# analogBoardV1_2.net
KiCad netlist of a schematic drawn in EAGLE
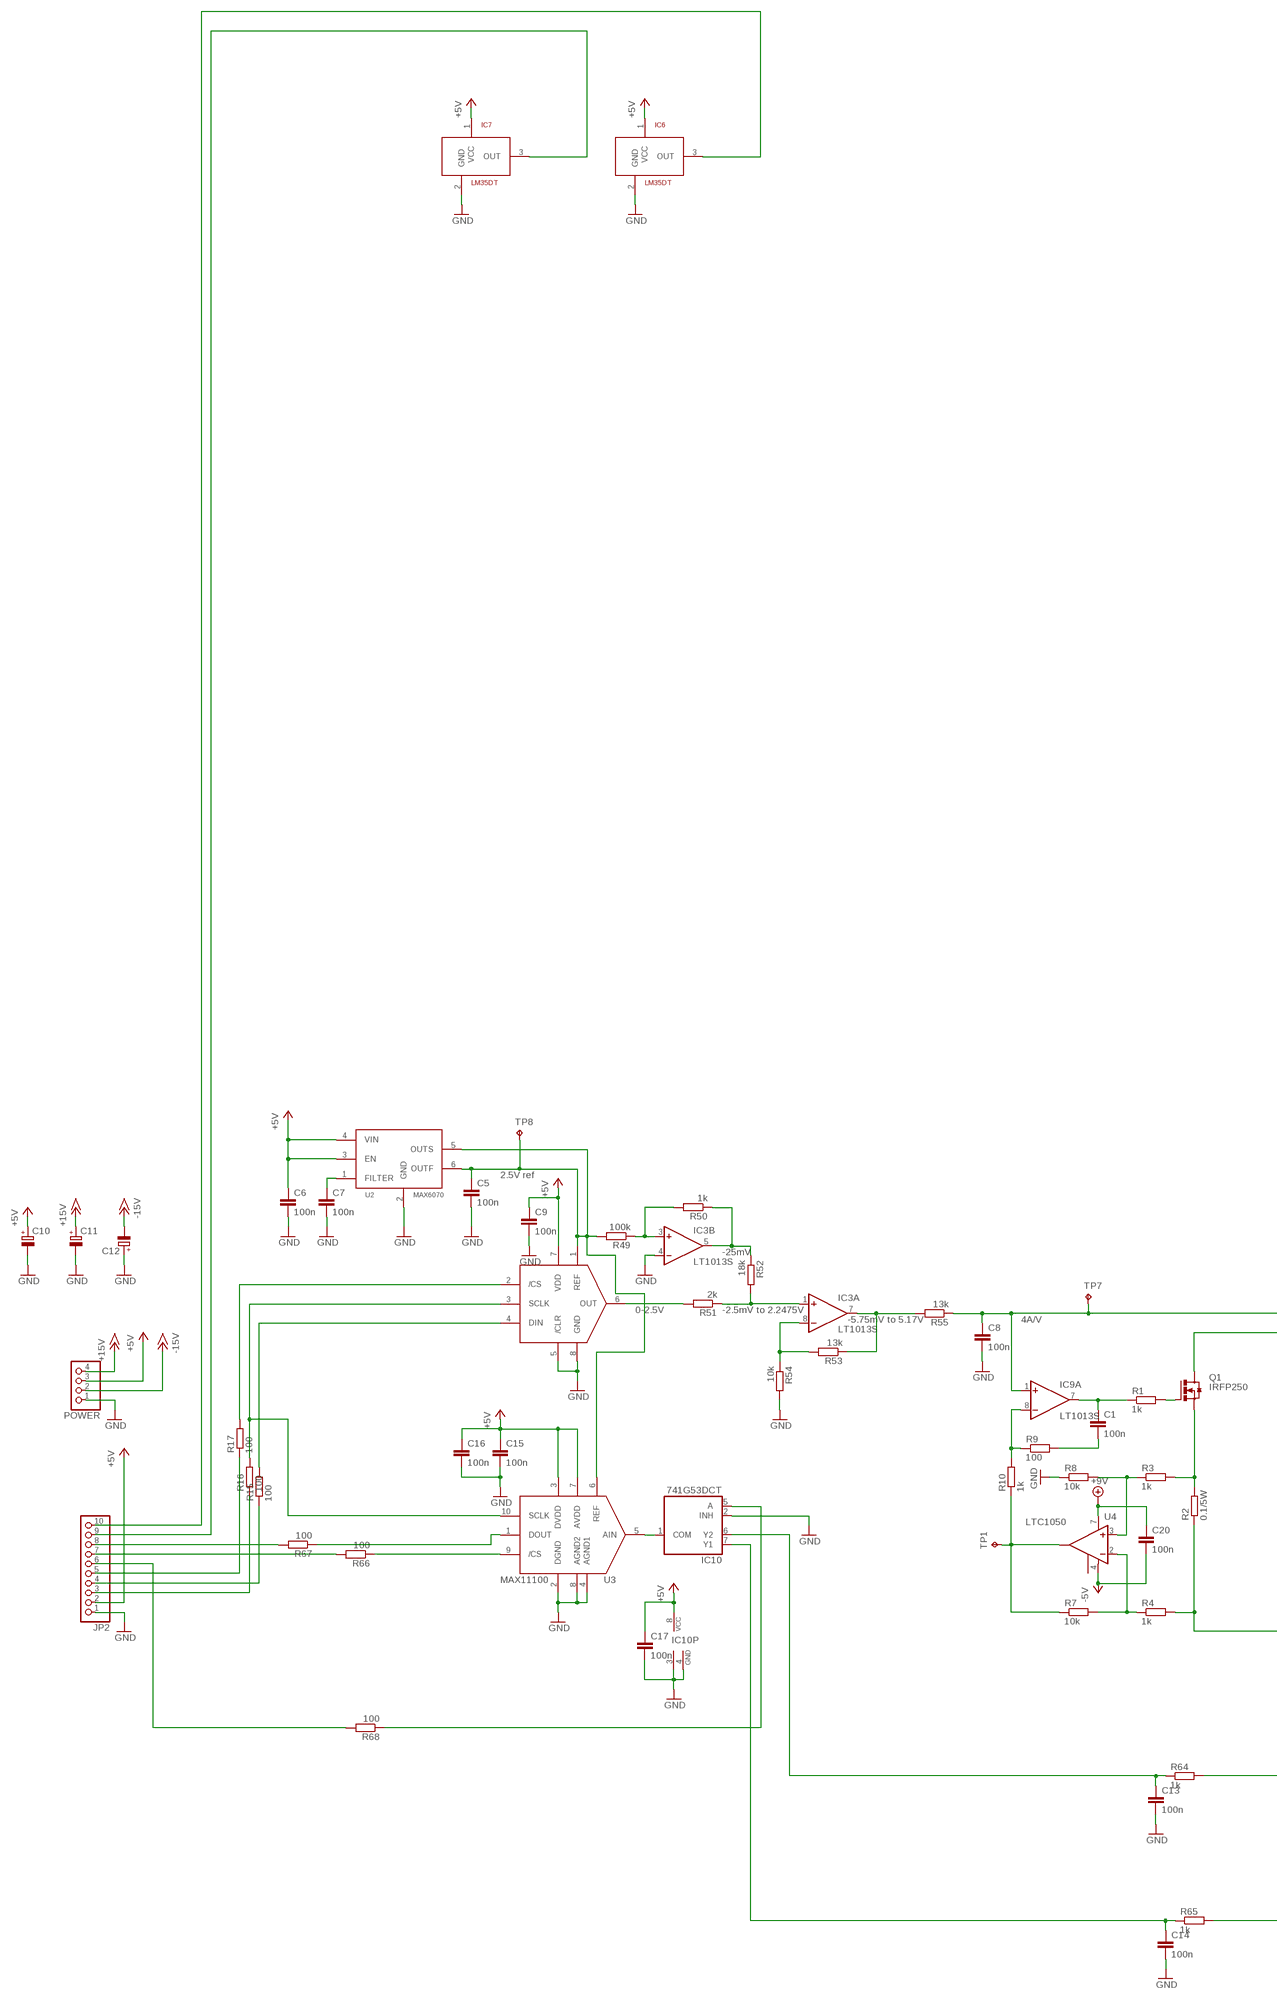
[diagram p0: schematic, sheet 1, part 1 of 2]
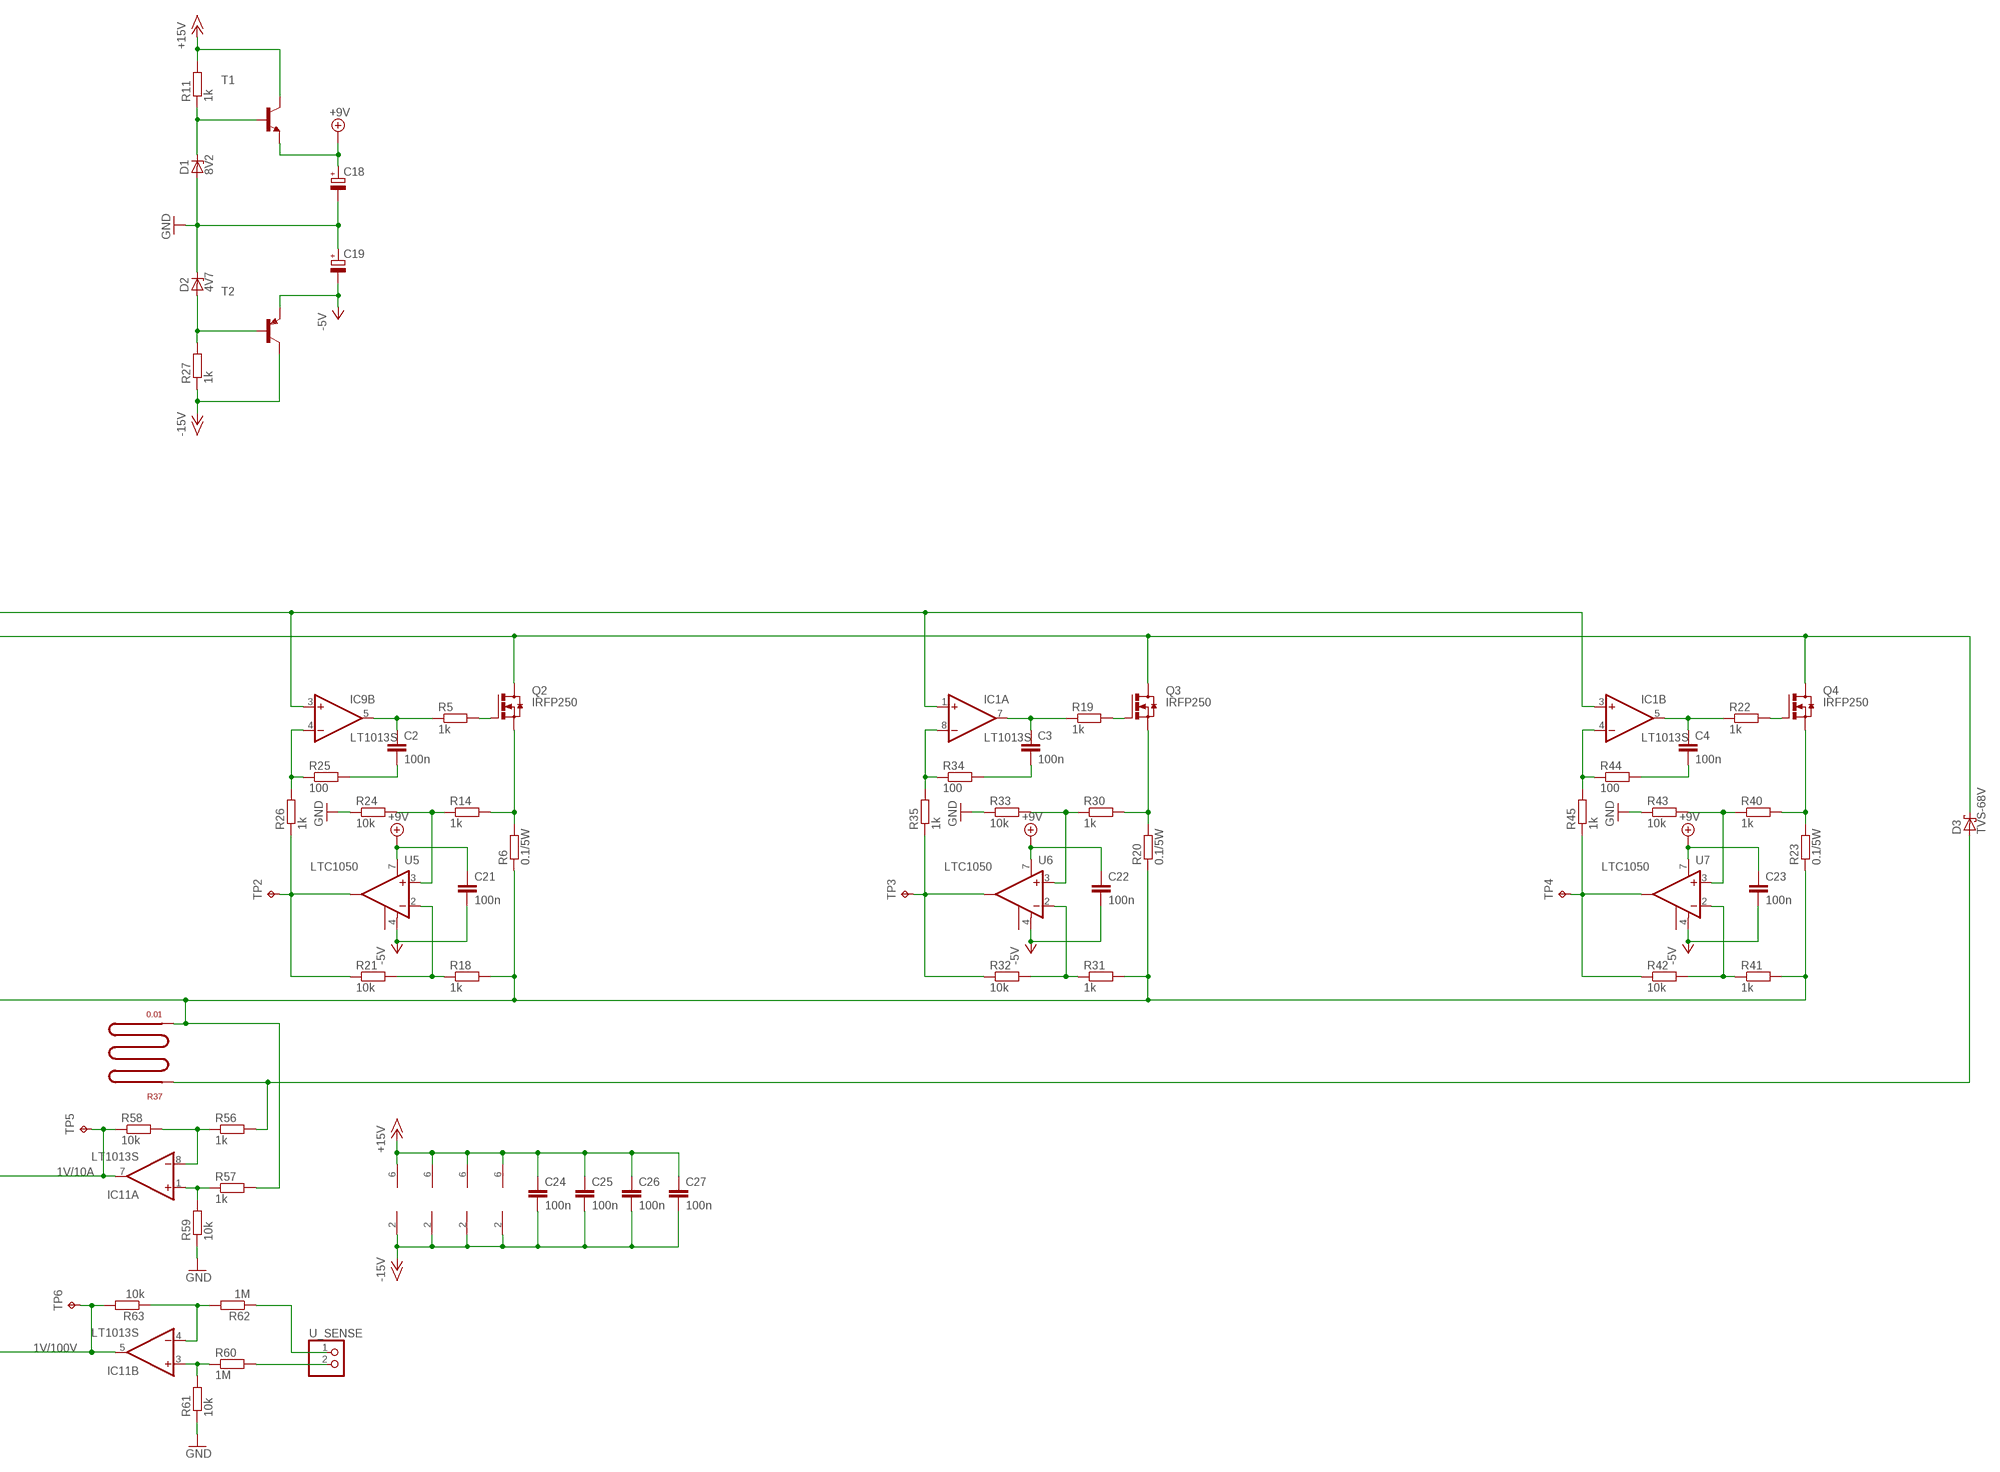
[diagram p1: schematic, sheet 1, part 2 of 2]

(export (version "E")
  (design (tool "Eeschema 10.0.6"))
  (components
    (comp (ref "C1")
      (value "100n")
      (footprint "eagle-import:C0603K")
      (libsource (lib "eagle-import") (part "C-EUC0603K"))
    )
    (comp (ref "C2")
      (value "100n")
      (footprint "eagle-import:C0603K")
      (libsource (lib "eagle-import") (part "C-EUC0603K"))
    )
    (comp (ref "C3")
      (value "100n")
      (footprint "eagle-import:C0603K")
      (libsource (lib "eagle-import") (part "C-EUC0603K"))
    )
    (comp (ref "C4")
      (value "100n")
      (footprint "eagle-import:C0603K")
      (libsource (lib "eagle-import") (part "C-EUC0603K"))
    )
    (comp (ref "C5")
      (value "100n")
      (footprint "eagle-import:C0603K")
      (libsource (lib "eagle-import") (part "C-EUC0603K"))
    )
    (comp (ref "C6")
      (value "100n")
      (footprint "eagle-import:C0603K")
      (libsource (lib "eagle-import") (part "C-EUC0603K"))
    )
    (comp (ref "C7")
      (value "100n")
      (footprint "eagle-import:C0603K")
      (libsource (lib "eagle-import") (part "C-EUC0603K"))
    )
    (comp (ref "C8")
      (value "100n")
      (footprint "eagle-import:C0603K")
      (libsource (lib "eagle-import") (part "C-EUC0603K"))
    )
    (comp (ref "C9")
      (value "100n")
      (footprint "eagle-import:C0603K")
      (libsource (lib "eagle-import") (part "C-EUC0603K"))
    )
    (comp (ref "C10")
      (value "CPOL-EUE2.5-6")
      (footprint "eagle-import:E2,5-6")
      (libsource (lib "eagle-import") (part "CPOL-EUE2.5-6"))
    )
    (comp (ref "C11")
      (value "CPOL-EUE2.5-6")
      (footprint "eagle-import:E2,5-6")
      (libsource (lib "eagle-import") (part "CPOL-EUE2.5-6"))
    )
    (comp (ref "C12")
      (value "CPOL-EUE2.5-6")
      (footprint "eagle-import:E2,5-6")
      (libsource (lib "eagle-import") (part "CPOL-EUE2.5-6"))
    )
    (comp (ref "C13")
      (value "100n")
      (footprint "eagle-import:C0603K")
      (libsource (lib "eagle-import") (part "C-EUC0603K"))
    )
    (comp (ref "C14")
      (value "100n")
      (footprint "eagle-import:C0603K")
      (libsource (lib "eagle-import") (part "C-EUC0603K"))
    )
    (comp (ref "C15")
      (value "100n")
      (footprint "eagle-import:C0603K")
      (libsource (lib "eagle-import") (part "C-EUC0603K"))
    )
    (comp (ref "C16")
      (value "100n")
      (footprint "eagle-import:C0603K")
      (libsource (lib "eagle-import") (part "C-EUC0603K"))
    )
    (comp (ref "C17")
      (value "100n")
      (footprint "eagle-import:C0603K")
      (libsource (lib "eagle-import") (part "C-EUC0603K"))
    )
    (comp (ref "C18")
      (value "CPOL-EUE2.5-6")
      (footprint "eagle-import:E2,5-6")
      (libsource (lib "eagle-import") (part "CPOL-EUE2.5-6"))
    )
    (comp (ref "C19")
      (value "CPOL-EUE2.5-6")
      (footprint "eagle-import:E2,5-6")
      (libsource (lib "eagle-import") (part "CPOL-EUE2.5-6"))
    )
    (comp (ref "C20")
      (value "100n")
      (footprint "eagle-import:C0603K")
      (libsource (lib "eagle-import") (part "C-EUC0603K"))
    )
    (comp (ref "C21")
      (value "100n")
      (footprint "eagle-import:C0603K")
      (libsource (lib "eagle-import") (part "C-EUC0603K"))
    )
    (comp (ref "C22")
      (value "100n")
      (footprint "eagle-import:C0603K")
      (libsource (lib "eagle-import") (part "C-EUC0603K"))
    )
    (comp (ref "C23")
      (value "100n")
      (footprint "eagle-import:C0603K")
      (libsource (lib "eagle-import") (part "C-EUC0603K"))
    )
    (comp (ref "C24")
      (value "100n")
      (footprint "eagle-import:C0603K")
      (libsource (lib "eagle-import") (part "C-EUC0603K"))
    )
    (comp (ref "C25")
      (value "100n")
      (footprint "eagle-import:C0603K")
      (libsource (lib "eagle-import") (part "C-EUC0603K"))
    )
    (comp (ref "C26")
      (value "100n")
      (footprint "eagle-import:C0603K")
      (libsource (lib "eagle-import") (part "C-EUC0603K"))
    )
    (comp (ref "C27")
      (value "100n")
      (footprint "eagle-import:C0603K")
      (libsource (lib "eagle-import") (part "C-EUC0603K"))
    )
    (comp (ref "D1")
      (value "8V2")
      (footprint "eagle-import:SOT23")
      (libsource (lib "eagle-import") (part "ZENER-DIODESOT23"))
    )
    (comp (ref "D2")
      (value "4V7")
      (footprint "eagle-import:SOT23")
      (libsource (lib "eagle-import") (part "ZENER-DIODESOT23"))
    )
    (comp (ref "D3")
      (value "TVS-68V")
      (footprint "eagle-import:CB429-15")
      (libsource (lib "eagle-import") (part "SCHOTTKY-DIODECB429-15"))
    )
    (comp (ref "IC1")
      (value "LT1013S")
      (footprint "eagle-import:SO08")
      (libsource (lib "eagle-import") (part "LT1013S"))
    )
    (comp (ref "IC3")
      (value "LT1013S")
      (footprint "eagle-import:SO08")
      (libsource (lib "eagle-import") (part "LT1013S"))
    )
    (comp (ref "IC6")
      (value "LM35DT")
      (footprint "eagle-import:TO220V")
      (libsource (lib "eagle-import") (part "LM35DT"))
    )
    (comp (ref "IC7")
      (value "LM35DT")
      (footprint "eagle-import:TO220V")
      (libsource (lib "eagle-import") (part "LM35DT"))
    )
    (comp (ref "IC9")
      (value "LT1013S")
      (footprint "eagle-import:SO08")
      (libsource (lib "eagle-import") (part "LT1013S"))
    )
    (comp (ref "IC10")
      (value "741G53DCT")
      (footprint "eagle-import:DCT_R-PDSO-G8")
      (libsource (lib "eagle-import") (part "741G53DCT"))
    )
    (comp (ref "IC11")
      (value "LT1013S")
      (footprint "eagle-import:SO08")
      (libsource (lib "eagle-import") (part "LT1013S"))
    )
    (comp (ref "JP2")
      (value "PINHD-1X10")
      (footprint "eagle-import:1X10")
      (libsource (lib "eagle-import") (part "PINHD-1X10"))
    )
    (comp (ref "POWER")
      (value "PINHD-1X4")
      (footprint "eagle-import:1X04")
      (libsource (lib "eagle-import") (part "PINHD-1X4"))
    )
    (comp (ref "Q1")
      (value "IRFP250")
      (footprint "eagle-import:TO-247AD-V")
      (libsource (lib "eagle-import") (part "IRFP250"))
    )
    (comp (ref "Q2")
      (value "IRFP250")
      (footprint "eagle-import:TO-247AD-V")
      (libsource (lib "eagle-import") (part "IRFP250"))
    )
    (comp (ref "Q3")
      (value "IRFP250")
      (footprint "eagle-import:TO-247AD-V")
      (libsource (lib "eagle-import") (part "IRFP250"))
    )
    (comp (ref "Q4")
      (value "IRFP250")
      (footprint "eagle-import:TO-247AD-V")
      (libsource (lib "eagle-import") (part "IRFP250"))
    )
    (comp (ref "R1")
      (value "1k")
      (footprint "eagle-import:R0603")
      (libsource (lib "eagle-import") (part "R-EU_R0603"))
    )
    (comp (ref "R2")
      (value "0.1/5W")
      (footprint "eagle-import:5WAXIAL")
      (libsource (lib "eagle-import") (part "5WAXIAL"))
    )
    (comp (ref "R3")
      (value "1k")
      (footprint "eagle-import:R0603")
      (libsource (lib "eagle-import") (part "R-EU_R0603"))
    )
    (comp (ref "R4")
      (value "1k")
      (footprint "eagle-import:R0603")
      (libsource (lib "eagle-import") (part "R-EU_R0603"))
    )
    (comp (ref "R5")
      (value "1k")
      (footprint "eagle-import:R0603")
      (libsource (lib "eagle-import") (part "R-EU_R0603"))
    )
    (comp (ref "R6")
      (value "0.1/5W")
      (footprint "eagle-import:5WAXIAL")
      (libsource (lib "eagle-import") (part "5WAXIAL"))
    )
    (comp (ref "R7")
      (value "10k")
      (footprint "eagle-import:R0603")
      (libsource (lib "eagle-import") (part "R-EU_R0603"))
    )
    (comp (ref "R8")
      (value "10k")
      (footprint "eagle-import:R0603")
      (libsource (lib "eagle-import") (part "R-EU_R0603"))
    )
    (comp (ref "R9")
      (value "100")
      (footprint "eagle-import:R0603")
      (libsource (lib "eagle-import") (part "R-EU_R0603"))
    )
    (comp (ref "R10")
      (value "1k")
      (footprint "eagle-import:R0603")
      (libsource (lib "eagle-import") (part "R-EU_R0603"))
    )
    (comp (ref "R11")
      (value "1k")
      (footprint "eagle-import:R0603")
      (libsource (lib "eagle-import") (part "R-EU_R0603"))
    )
    (comp (ref "R14")
      (value "1k")
      (footprint "eagle-import:R0603")
      (libsource (lib "eagle-import") (part "R-EU_R0603"))
    )
    (comp (ref "R15")
      (value "100")
      (footprint "eagle-import:R0603")
      (libsource (lib "eagle-import") (part "R-EU_R0603"))
    )
    (comp (ref "R16")
      (value "100")
      (footprint "eagle-import:R0603")
      (libsource (lib "eagle-import") (part "R-EU_R0603"))
    )
    (comp (ref "R17")
      (value "100")
      (footprint "eagle-import:R0603")
      (libsource (lib "eagle-import") (part "R-EU_R0603"))
    )
    (comp (ref "R18")
      (value "1k")
      (footprint "eagle-import:R0603")
      (libsource (lib "eagle-import") (part "R-EU_R0603"))
    )
    (comp (ref "R19")
      (value "1k")
      (footprint "eagle-import:R0603")
      (libsource (lib "eagle-import") (part "R-EU_R0603"))
    )
    (comp (ref "R20")
      (value "0.1/5W")
      (footprint "eagle-import:5WAXIAL")
      (libsource (lib "eagle-import") (part "5WAXIAL"))
    )
    (comp (ref "R21")
      (value "10k")
      (footprint "eagle-import:R0603")
      (libsource (lib "eagle-import") (part "R-EU_R0603"))
    )
    (comp (ref "R22")
      (value "1k")
      (footprint "eagle-import:R0603")
      (libsource (lib "eagle-import") (part "R-EU_R0603"))
    )
    (comp (ref "R23")
      (value "0.1/5W")
      (footprint "eagle-import:5WAXIAL")
      (libsource (lib "eagle-import") (part "5WAXIAL"))
    )
    (comp (ref "R24")
      (value "10k")
      (footprint "eagle-import:R0603")
      (libsource (lib "eagle-import") (part "R-EU_R0603"))
    )
    (comp (ref "R25")
      (value "100")
      (footprint "eagle-import:R0603")
      (libsource (lib "eagle-import") (part "R-EU_R0603"))
    )
    (comp (ref "R26")
      (value "1k")
      (footprint "eagle-import:R0603")
      (libsource (lib "eagle-import") (part "R-EU_R0603"))
    )
    (comp (ref "R27")
      (value "1k")
      (footprint "eagle-import:R0603")
      (libsource (lib "eagle-import") (part "R-EU_R0603"))
    )
    (comp (ref "R30")
      (value "1k")
      (footprint "eagle-import:R0603")
      (libsource (lib "eagle-import") (part "R-EU_R0603"))
    )
    (comp (ref "R31")
      (value "1k")
      (footprint "eagle-import:R0603")
      (libsource (lib "eagle-import") (part "R-EU_R0603"))
    )
    (comp (ref "R32")
      (value "10k")
      (footprint "eagle-import:R0603")
      (libsource (lib "eagle-import") (part "R-EU_R0603"))
    )
    (comp (ref "R33")
      (value "10k")
      (footprint "eagle-import:R0603")
      (libsource (lib "eagle-import") (part "R-EU_R0603"))
    )
    (comp (ref "R34")
      (value "100")
      (footprint "eagle-import:R0603")
      (libsource (lib "eagle-import") (part "R-EU_R0603"))
    )
    (comp (ref "R35")
      (value "1k")
      (footprint "eagle-import:R0603")
      (libsource (lib "eagle-import") (part "R-EU_R0603"))
    )
    (comp (ref "R37")
      (value "0.01")
      (footprint "eagle-import:COPPERSHUNT")
      (libsource (lib "eagle-import") (part "SHUNT"))
    )
    (comp (ref "R40")
      (value "1k")
      (footprint "eagle-import:R0603")
      (libsource (lib "eagle-import") (part "R-EU_R0603"))
    )
    (comp (ref "R41")
      (value "1k")
      (footprint "eagle-import:R0603")
      (libsource (lib "eagle-import") (part "R-EU_R0603"))
    )
    (comp (ref "R42")
      (value "10k")
      (footprint "eagle-import:R0603")
      (libsource (lib "eagle-import") (part "R-EU_R0603"))
    )
    (comp (ref "R43")
      (value "10k")
      (footprint "eagle-import:R0603")
      (libsource (lib "eagle-import") (part "R-EU_R0603"))
    )
    (comp (ref "R44")
      (value "100")
      (footprint "eagle-import:R0603")
      (libsource (lib "eagle-import") (part "R-EU_R0603"))
    )
    (comp (ref "R45")
      (value "1k")
      (footprint "eagle-import:R0603")
      (libsource (lib "eagle-import") (part "R-EU_R0603"))
    )
    (comp (ref "R49")
      (value "100k")
      (footprint "eagle-import:R0603")
      (libsource (lib "eagle-import") (part "R-EU_R0603"))
    )
    (comp (ref "R50")
      (value "1k")
      (footprint "eagle-import:R0603")
      (libsource (lib "eagle-import") (part "R-EU_R0603"))
    )
    (comp (ref "R51")
      (value "2k")
      (footprint "eagle-import:R0603")
      (libsource (lib "eagle-import") (part "R-EU_R0603"))
    )
    (comp (ref "R52")
      (value "18k")
      (footprint "eagle-import:R0603")
      (libsource (lib "eagle-import") (part "R-EU_R0603"))
    )
    (comp (ref "R53")
      (value "13k")
      (footprint "eagle-import:R0603")
      (libsource (lib "eagle-import") (part "R-EU_R0603"))
    )
    (comp (ref "R54")
      (value "10k")
      (footprint "eagle-import:R0603")
      (libsource (lib "eagle-import") (part "R-EU_R0603"))
    )
    (comp (ref "R55")
      (value "13k")
      (footprint "eagle-import:R0603")
      (libsource (lib "eagle-import") (part "R-EU_R0603"))
    )
    (comp (ref "R56")
      (value "1k")
      (footprint "eagle-import:R0603")
      (libsource (lib "eagle-import") (part "R-EU_R0603"))
    )
    (comp (ref "R57")
      (value "1k")
      (footprint "eagle-import:R0603")
      (libsource (lib "eagle-import") (part "R-EU_R0603"))
    )
    (comp (ref "R58")
      (value "10k")
      (footprint "eagle-import:R0603")
      (libsource (lib "eagle-import") (part "R-EU_R0603"))
    )
    (comp (ref "R59")
      (value "10k")
      (footprint "eagle-import:R0603")
      (libsource (lib "eagle-import") (part "R-EU_R0603"))
    )
    (comp (ref "R60")
      (value "1M")
      (footprint "eagle-import:R0603")
      (libsource (lib "eagle-import") (part "R-EU_R0603"))
    )
    (comp (ref "R61")
      (value "10k")
      (footprint "eagle-import:R0603")
      (libsource (lib "eagle-import") (part "R-EU_R0603"))
    )
    (comp (ref "R62")
      (value "1M")
      (footprint "eagle-import:R0603")
      (libsource (lib "eagle-import") (part "R-EU_R0603"))
    )
    (comp (ref "R63")
      (value "10k")
      (footprint "eagle-import:R0603")
      (libsource (lib "eagle-import") (part "R-EU_R0603"))
    )
    (comp (ref "R64")
      (value "1k")
      (footprint "eagle-import:R0603")
      (libsource (lib "eagle-import") (part "R-EU_R0603"))
    )
    (comp (ref "R65")
      (value "1k")
      (footprint "eagle-import:R0603")
      (libsource (lib "eagle-import") (part "R-EU_R0603"))
    )
    (comp (ref "R66")
      (value "100")
      (footprint "eagle-import:R0603")
      (libsource (lib "eagle-import") (part "R-EU_R0603"))
    )
    (comp (ref "R67")
      (value "100")
      (footprint "eagle-import:R0603")
      (libsource (lib "eagle-import") (part "R-EU_R0603"))
    )
    (comp (ref "R68")
      (value "100")
      (footprint "eagle-import:R0603")
      (libsource (lib "eagle-import") (part "R-EU_R0603"))
    )
    (comp (ref "T1")
      (value "BC817-16-NPN-SOT23-BEC")
      (footprint "eagle-import:SOT23-BEC")
      (libsource (lib "eagle-import") (part "-NPN-SOT23-BECBC817-16"))
    )
    (comp (ref "T2")
      (value "BC807-16-PNP-SOT23-BEC")
      (footprint "eagle-import:SOT23-BEC")
      (libsource (lib "eagle-import") (part "-PNP-SOT23-BECBC807-16"))
    )
    (comp (ref "TP1")
      (value "TPB1,27")
      (footprint "eagle-import:B1,27")
      (libsource (lib "eagle-import") (part "TPB1,27"))
    )
    (comp (ref "TP2")
      (value "TPB1,27")
      (footprint "eagle-import:B1,27")
      (libsource (lib "eagle-import") (part "TPB1,27"))
    )
    (comp (ref "TP3")
      (value "TPB1,27")
      (footprint "eagle-import:B1,27")
      (libsource (lib "eagle-import") (part "TPB1,27"))
    )
    (comp (ref "TP4")
      (value "TPB1,27")
      (footprint "eagle-import:B1,27")
      (libsource (lib "eagle-import") (part "TPB1,27"))
    )
    (comp (ref "TP5")
      (value "TPB1,27")
      (footprint "eagle-import:B1,27")
      (libsource (lib "eagle-import") (part "TPB1,27"))
    )
    (comp (ref "TP6")
      (value "TPB1,27")
      (footprint "eagle-import:B1,27")
      (libsource (lib "eagle-import") (part "TPB1,27"))
    )
    (comp (ref "TP7")
      (value "TPB1,27")
      (footprint "eagle-import:B1,27")
      (libsource (lib "eagle-import") (part "TPB1,27"))
    )
    (comp (ref "TP8")
      (value "TPB1,27")
      (footprint "eagle-import:B1,27")
      (libsource (lib "eagle-import") (part "TPB1,27"))
    )
    (comp (ref "U1")
      (value "MAX5216")
      (footprint "eagle-import:UMAX8")
      (libsource (lib "eagle-import") (part "MAX5216"))
    )
    (comp (ref "U2")
      (value "MAX6070")
      (footprint "eagle-import:SOT23-6L")
      (libsource (lib "eagle-import") (part "MAX6070"))
    )
    (comp (ref "U3")
      (value "MAX11100")
      (footprint "eagle-import:UMAX10")
      (libsource (lib "eagle-import") (part "MAX11100"))
    )
    (comp (ref "U4")
      (value "LTC1050")
      (footprint "eagle-import:SOIC8")
      (libsource (lib "eagle-import") (part "LTC1050"))
    )
    (comp (ref "U5")
      (value "LTC1050")
      (footprint "eagle-import:SOIC8")
      (libsource (lib "eagle-import") (part "LTC1050"))
    )
    (comp (ref "U6")
      (value "LTC1050")
      (footprint "eagle-import:SOIC8")
      (libsource (lib "eagle-import") (part "LTC1050"))
    )
    (comp (ref "U7")
      (value "LTC1050")
      (footprint "eagle-import:SOIC8")
      (libsource (lib "eagle-import") (part "LTC1050"))
    )
    (comp (ref "U_SENSE")
      (value "PINHD-1X2")
      (footprint "eagle-import:1X02")
      (libsource (lib "eagle-import") (part "PINHD-1X2"))
    )
  )
  (nets
    (net (code "1") (name "+5V") (class "Default")
      (node (ref "C10") (pin "+") (pinfunction "+_+") (pintype "passive"))
      (node (ref "C15") (pin "1") (pinfunction "1_1") (pintype "passive"))
      (node (ref "C16") (pin "1") (pinfunction "1_1") (pintype "passive"))
      (node (ref "C17") (pin "1") (pinfunction "1_1") (pintype "passive"))
      (node (ref "C6") (pin "1") (pinfunction "1_1") (pintype "passive"))
      (node (ref "C9") (pin "1") (pinfunction "1_1") (pintype "passive"))
      (node (ref "IC10") (pin "8") (pinfunction "VCC_8") (pintype "power_in"))
      (node (ref "IC6") (pin "1") (pinfunction "VCC_1") (pintype "bidirectional"))
      (node (ref "IC7") (pin "1") (pinfunction "VCC_1") (pintype "bidirectional"))
      (node (ref "JP2") (pin "2") (pinfunction "2_2") (pintype "passive"))
      (node (ref "POWER") (pin "3") (pinfunction "3_3") (pintype "passive"))
      (node (ref "U1") (pin "7") (pinfunction "VDD_7") (pintype "bidirectional"))
      (node (ref "U2") (pin "3") (pinfunction "EN_3") (pintype "bidirectional"))
      (node (ref "U2") (pin "4") (pinfunction "VIN_4") (pintype "bidirectional"))
      (node (ref "U3") (pin "3") (pinfunction "DVDD_3") (pintype "bidirectional"))
      (node (ref "U3") (pin "7") (pinfunction "AVDD_7") (pintype "bidirectional"))
    )
    (net (code "2") (name "+9V") (class "Default")
      (node (ref "C18") (pin "+") (pinfunction "+_+") (pintype "passive"))
      (node (ref "C20") (pin "1") (pinfunction "1_1") (pintype "passive"))
      (node (ref "C21") (pin "1") (pinfunction "1_1") (pintype "passive"))
      (node (ref "C22") (pin "1") (pinfunction "1_1") (pintype "passive"))
      (node (ref "C23") (pin "1") (pinfunction "1_1") (pintype "passive"))
      (node (ref "T1") (pin "E") (pinfunction "E_E") (pintype "passive"))
      (node (ref "U4") (pin "7") (pinfunction "V+_7") (pintype "power_in"))
      (node (ref "U5") (pin "7") (pinfunction "V+_7") (pintype "power_in"))
      (node (ref "U6") (pin "7") (pinfunction "V+_7") (pintype "power_in"))
      (node (ref "U7") (pin "7") (pinfunction "V+_7") (pintype "power_in"))
    )
    (net (code "3") (name "+15V") (class "Default")
      (node (ref "C11") (pin "+") (pinfunction "+_+") (pintype "passive"))
      (node (ref "C24") (pin "1") (pinfunction "1_1") (pintype "passive"))
      (node (ref "C25") (pin "1") (pinfunction "1_1") (pintype "passive"))
      (node (ref "C26") (pin "1") (pinfunction "1_1") (pintype "passive"))
      (node (ref "C27") (pin "1") (pinfunction "1_1") (pintype "passive"))
      (node (ref "IC1") (pin "6") (pinfunction "V+_6") (pintype "power_in"))
      (node (ref "IC11") (pin "6") (pinfunction "V+_6") (pintype "power_in"))
      (node (ref "IC3") (pin "6") (pinfunction "V+_6") (pintype "power_in"))
      (node (ref "IC9") (pin "6") (pinfunction "V+_6") (pintype "power_in"))
      (node (ref "POWER") (pin "4") (pinfunction "4_4") (pintype "passive"))
      (node (ref "R11") (pin "2") (pinfunction "2_2") (pintype "passive"))
      (node (ref "T1") (pin "C") (pinfunction "C_C") (pintype "passive"))
    )
    (net (code "4") (name "-5V") (class "Default")
      (node (ref "C19") (pin "-") (pinfunction "-_-") (pintype "passive"))
      (node (ref "C20") (pin "2") (pinfunction "2_2") (pintype "passive"))
      (node (ref "C21") (pin "2") (pinfunction "2_2") (pintype "passive"))
      (node (ref "C22") (pin "2") (pinfunction "2_2") (pintype "passive"))
      (node (ref "C23") (pin "2") (pinfunction "2_2") (pintype "passive"))
      (node (ref "T2") (pin "E") (pinfunction "E_E") (pintype "passive"))
      (node (ref "U4") (pin "4") (pinfunction "V-_4") (pintype "power_in"))
      (node (ref "U5") (pin "4") (pinfunction "V-_4") (pintype "power_in"))
      (node (ref "U6") (pin "4") (pinfunction "V-_4") (pintype "power_in"))
      (node (ref "U7") (pin "4") (pinfunction "V-_4") (pintype "power_in"))
    )
    (net (code "5") (name "-15V") (class "Default")
      (node (ref "C12") (pin "-") (pinfunction "-_-") (pintype "passive"))
      (node (ref "C24") (pin "2") (pinfunction "2_2") (pintype "passive"))
      (node (ref "C25") (pin "2") (pinfunction "2_2") (pintype "passive"))
      (node (ref "C26") (pin "2") (pinfunction "2_2") (pintype "passive"))
      (node (ref "C27") (pin "2") (pinfunction "2_2") (pintype "passive"))
      (node (ref "IC1") (pin "2") (pinfunction "V-_2") (pintype "power_in"))
      (node (ref "IC11") (pin "2") (pinfunction "V-_2") (pintype "power_in"))
      (node (ref "IC3") (pin "2") (pinfunction "V-_2") (pintype "power_in"))
      (node (ref "IC9") (pin "2") (pinfunction "V-_2") (pintype "power_in"))
      (node (ref "POWER") (pin "2") (pinfunction "2_2") (pintype "passive"))
      (node (ref "R27") (pin "1") (pinfunction "1_1") (pintype "passive"))
      (node (ref "T2") (pin "C") (pinfunction "C_C") (pintype "passive"))
    )
    (net (code "6") (name "GND") (class "Default")
      (node (ref "C10") (pin "-") (pinfunction "-_-") (pintype "passive"))
      (node (ref "C11") (pin "-") (pinfunction "-_-") (pintype "passive"))
      (node (ref "C12") (pin "+") (pinfunction "+_+") (pintype "passive"))
      (node (ref "C13") (pin "2") (pinfunction "2_2") (pintype "passive"))
      (node (ref "C14") (pin "2") (pinfunction "2_2") (pintype "passive"))
      (node (ref "C15") (pin "2") (pinfunction "2_2") (pintype "passive"))
      (node (ref "C16") (pin "2") (pinfunction "2_2") (pintype "passive"))
      (node (ref "C17") (pin "2") (pinfunction "2_2") (pintype "passive"))
      (node (ref "C18") (pin "-") (pinfunction "-_-") (pintype "passive"))
      (node (ref "C19") (pin "+") (pinfunction "+_+") (pintype "passive"))
      (node (ref "C5") (pin "2") (pinfunction "2_2") (pintype "passive"))
      (node (ref "C6") (pin "2") (pinfunction "2_2") (pintype "passive"))
      (node (ref "C7") (pin "2") (pinfunction "2_2") (pintype "passive"))
      (node (ref "C8") (pin "2") (pinfunction "2_2") (pintype "passive"))
      (node (ref "C9") (pin "2") (pinfunction "2_2") (pintype "passive"))
      (node (ref "D1") (pin "1") (pinfunction "A_1") (pintype "passive"))
      (node (ref "D2") (pin "3") (pinfunction "C_3") (pintype "passive"))
      (node (ref "IC10") (pin "2") (pinfunction "INH_2") (pintype "input"))
      (node (ref "IC10") (pin "3") (pinfunction "GND_3") (pintype "power_in"))
      (node (ref "IC10") (pin "4") (pinfunction "GND_4") (pintype "power_in"))
      (node (ref "IC3") (pin "4") (pinfunction "-IN_4") (pintype "input"))
      (node (ref "IC6") (pin "2") (pinfunction "GND_2") (pintype "bidirectional"))
      (node (ref "IC7") (pin "2") (pinfunction "GND_2") (pintype "bidirectional"))
      (node (ref "JP2") (pin "1") (pinfunction "1_1") (pintype "passive"))
      (node (ref "POWER") (pin "1") (pinfunction "1_1") (pintype "passive"))
      (node (ref "R24") (pin "1") (pinfunction "1_1") (pintype "passive"))
      (node (ref "R33") (pin "1") (pinfunction "1_1") (pintype "passive"))
      (node (ref "R43") (pin "1") (pinfunction "1_1") (pintype "passive"))
      (node (ref "R54") (pin "2") (pinfunction "2_2") (pintype "passive"))
      (node (ref "R59") (pin "1") (pinfunction "1_1") (pintype "passive"))
      (node (ref "R61") (pin "1") (pinfunction "1_1") (pintype "passive"))
      (node (ref "R8") (pin "1") (pinfunction "1_1") (pintype "passive"))
      (node (ref "U1") (pin "5") (pinfunction "/CLR_5") (pintype "bidirectional"))
      (node (ref "U1") (pin "8") (pinfunction "GND_8") (pintype "bidirectional"))
      (node (ref "U2") (pin "2") (pinfunction "GND_2") (pintype "bidirectional"))
      (node (ref "U3") (pin "2") (pinfunction "DGND_2") (pintype "bidirectional"))
      (node (ref "U3") (pin "4") (pinfunction "AGND1_4") (pintype "bidirectional"))
      (node (ref "U3") (pin "8") (pinfunction "AGND2_8") (pintype "bidirectional"))
    )
    (net (code "7") (name "Net-(C1-Pad2)") (class "Default")
      (node (ref "C1") (pin "2") (pinfunction "2_2") (pintype "passive"))
      (node (ref "R9") (pin "2") (pinfunction "2_2") (pintype "passive"))
    )
    (net (code "8") (name "Net-(C2-Pad2)") (class "Default")
      (node (ref "C2") (pin "2") (pinfunction "2_2") (pintype "passive"))
      (node (ref "R25") (pin "2") (pinfunction "2_2") (pintype "passive"))
    )
    (net (code "9") (name "Net-(C3-Pad2)") (class "Default")
      (node (ref "C3") (pin "2") (pinfunction "2_2") (pintype "passive"))
      (node (ref "R34") (pin "2") (pinfunction "2_2") (pintype "passive"))
    )
    (net (code "10") (name "Net-(C4-Pad2)") (class "Default")
      (node (ref "C4") (pin "2") (pinfunction "2_2") (pintype "passive"))
      (node (ref "R44") (pin "2") (pinfunction "2_2") (pintype "passive"))
    )
    (net (code "11") (name "Net-(D1-C)") (class "Default")
      (node (ref "D1") (pin "3") (pinfunction "C_3") (pintype "passive"))
      (node (ref "R11") (pin "1") (pinfunction "1_1") (pintype "passive"))
      (node (ref "T1") (pin "B") (pinfunction "B_B") (pintype "passive"))
    )
    (net (code "12") (name "Net-(D2-A)") (class "Default")
      (node (ref "D2") (pin "1") (pinfunction "A_1") (pintype "passive"))
      (node (ref "R27") (pin "2") (pinfunction "2_2") (pintype "passive"))
      (node (ref "T2") (pin "B") (pinfunction "B_B") (pintype "passive"))
    )
    (net (code "13") (name "Net-(D3-PadA)") (class "Default")
      (node (ref "D3") (pin "A") (pinfunction "A_A") (pintype "passive"))
      (node (ref "R37") (pin "P$1") (pinfunction "P$1_P$1") (pintype "bidirectional"))
      (node (ref "R56") (pin "2") (pinfunction "2_2") (pintype "passive"))
    )
    (net (code "14") (name "Net-(D3-PadC)") (class "Default")
      (node (ref "D3") (pin "C") (pinfunction "C_C") (pintype "passive"))
      (node (ref "Q1") (pin "D") (pinfunction "D_D") (pintype "passive"))
      (node (ref "Q2") (pin "D") (pinfunction "D_D") (pintype "passive"))
      (node (ref "Q3") (pin "D") (pinfunction "D_D") (pintype "passive"))
      (node (ref "Q4") (pin "D") (pinfunction "D_D") (pintype "passive"))
    )
    (net (code "15") (name "Net-(IC1A-+IN)") (class "Default")
      (node (ref "C8") (pin "1") (pinfunction "1_1") (pintype "passive"))
      (node (ref "IC1") (pin "1") (pinfunction "+IN_1") (pintype "input"))
      (node (ref "IC1") (pin "3") (pinfunction "+IN_3") (pintype "input"))
      (node (ref "IC9") (pin "1") (pinfunction "+IN_1") (pintype "input"))
      (node (ref "IC9") (pin "3") (pinfunction "+IN_3") (pintype "input"))
      (node (ref "R55") (pin "1") (pinfunction "1_1") (pintype "passive"))
      (node (ref "TP7") (pin "TP") (pinfunction "TP_TP") (pintype "input"))
    )
    (net (code "16") (name "Net-(IC1A--IN)") (class "Default")
      (node (ref "IC1") (pin "8") (pinfunction "-IN_8") (pintype "input"))
      (node (ref "R34") (pin "1") (pinfunction "1_1") (pintype "passive"))
      (node (ref "R35") (pin "2") (pinfunction "2_2") (pintype "passive"))
    )
    (net (code "17") (name "Net-(IC1A-OUT)") (class "Default")
      (node (ref "C3") (pin "1") (pinfunction "1_1") (pintype "passive"))
      (node (ref "IC1") (pin "7") (pinfunction "OUT_7") (pintype "output"))
      (node (ref "R19") (pin "1") (pinfunction "1_1") (pintype "passive"))
    )
    (net (code "18") (name "Net-(IC1B--IN)") (class "Default")
      (node (ref "IC1") (pin "4") (pinfunction "-IN_4") (pintype "input"))
      (node (ref "R44") (pin "1") (pinfunction "1_1") (pintype "passive"))
      (node (ref "R45") (pin "2") (pinfunction "2_2") (pintype "passive"))
    )
    (net (code "19") (name "Net-(IC1B-OUT)") (class "Default")
      (node (ref "C4") (pin "1") (pinfunction "1_1") (pintype "passive"))
      (node (ref "IC1") (pin "5") (pinfunction "OUT_5") (pintype "output"))
      (node (ref "R22") (pin "1") (pinfunction "1_1") (pintype "passive"))
    )
    (net (code "20") (name "Net-(IC3A-+IN)") (class "Default")
      (node (ref "IC3") (pin "1") (pinfunction "+IN_1") (pintype "input"))
      (node (ref "R51") (pin "1") (pinfunction "1_1") (pintype "passive"))
      (node (ref "R52") (pin "2") (pinfunction "2_2") (pintype "passive"))
    )
    (net (code "21") (name "Net-(IC3A--IN)") (class "Default")
      (node (ref "IC3") (pin "8") (pinfunction "-IN_8") (pintype "input"))
      (node (ref "R53") (pin "2") (pinfunction "2_2") (pintype "passive"))
      (node (ref "R54") (pin "1") (pinfunction "1_1") (pintype "passive"))
    )
    (net (code "22") (name "Net-(IC3A-OUT)") (class "Default")
      (node (ref "IC3") (pin "7") (pinfunction "OUT_7") (pintype "output"))
      (node (ref "R53") (pin "1") (pinfunction "1_1") (pintype "passive"))
      (node (ref "R55") (pin "2") (pinfunction "2_2") (pintype "passive"))
    )
    (net (code "23") (name "Net-(IC3B-+IN)") (class "Default")
      (node (ref "IC3") (pin "3") (pinfunction "+IN_3") (pintype "input"))
      (node (ref "R49") (pin "1") (pinfunction "1_1") (pintype "passive"))
      (node (ref "R50") (pin "2") (pinfunction "2_2") (pintype "passive"))
    )
    (net (code "24") (name "Net-(IC3B-OUT)") (class "Default")
      (node (ref "IC3") (pin "5") (pinfunction "OUT_5") (pintype "output"))
      (node (ref "R50") (pin "1") (pinfunction "1_1") (pintype "passive"))
      (node (ref "R52") (pin "1") (pinfunction "1_1") (pintype "passive"))
    )
    (net (code "25") (name "Net-(IC6-OUT)") (class "Default")
      (node (ref "IC6") (pin "3") (pinfunction "OUT_3") (pintype "bidirectional"))
      (node (ref "JP2") (pin "10") (pinfunction "10_10") (pintype "passive"))
    )
    (net (code "26") (name "Net-(IC7-OUT)") (class "Default")
      (node (ref "IC7") (pin "3") (pinfunction "OUT_3") (pintype "bidirectional"))
      (node (ref "JP2") (pin "9") (pinfunction "9_9") (pintype "passive"))
    )
    (net (code "27") (name "Net-(IC9A--IN)") (class "Default")
      (node (ref "IC9") (pin "8") (pinfunction "-IN_8") (pintype "input"))
      (node (ref "R10") (pin "2") (pinfunction "2_2") (pintype "passive"))
      (node (ref "R9") (pin "1") (pinfunction "1_1") (pintype "passive"))
    )
    (net (code "28") (name "Net-(IC9A-OUT)") (class "Default")
      (node (ref "C1") (pin "1") (pinfunction "1_1") (pintype "passive"))
      (node (ref "IC9") (pin "7") (pinfunction "OUT_7") (pintype "output"))
      (node (ref "R1") (pin "1") (pinfunction "1_1") (pintype "passive"))
    )
    (net (code "29") (name "Net-(IC9B--IN)") (class "Default")
      (node (ref "IC9") (pin "4") (pinfunction "-IN_4") (pintype "input"))
      (node (ref "R25") (pin "1") (pinfunction "1_1") (pintype "passive"))
      (node (ref "R26") (pin "2") (pinfunction "2_2") (pintype "passive"))
    )
    (net (code "30") (name "Net-(IC9B-OUT)") (class "Default")
      (node (ref "C2") (pin "1") (pinfunction "1_1") (pintype "passive"))
      (node (ref "IC9") (pin "5") (pinfunction "OUT_5") (pintype "output"))
      (node (ref "R5") (pin "1") (pinfunction "1_1") (pintype "passive"))
    )
    (net (code "31") (name "Net-(IC10A-A)") (class "Default")
      (node (ref "IC10") (pin "5") (pinfunction "A_5") (pintype "input"))
      (node (ref "R68") (pin "1") (pinfunction "1_1") (pintype "passive"))
    )
    (net (code "32") (name "Net-(IC10A-COM)") (class "Default")
      (node (ref "IC10") (pin "1") (pinfunction "COM_1") (pintype "bidirectional"))
      (node (ref "U3") (pin "5") (pinfunction "AIN_5") (pintype "bidirectional"))
    )
    (net (code "33") (name "Net-(IC10A-Y1)") (class "Default")
      (node (ref "C14") (pin "1") (pinfunction "1_1") (pintype "passive"))
      (node (ref "IC10") (pin "7") (pinfunction "Y1_7") (pintype "bidirectional"))
      (node (ref "R65") (pin "1") (pinfunction "1_1") (pintype "passive"))
    )
    (net (code "34") (name "Net-(IC10A-Y2)") (class "Default")
      (node (ref "C13") (pin "1") (pinfunction "1_1") (pintype "passive"))
      (node (ref "IC10") (pin "6") (pinfunction "Y2_6") (pintype "bidirectional"))
      (node (ref "R64") (pin "1") (pinfunction "1_1") (pintype "passive"))
    )
    (net (code "35") (name "Net-(IC11A-+IN)") (class "Default")
      (node (ref "IC11") (pin "1") (pinfunction "+IN_1") (pintype "input"))
      (node (ref "R57") (pin "1") (pinfunction "1_1") (pintype "passive"))
      (node (ref "R59") (pin "2") (pinfunction "2_2") (pintype "passive"))
    )
    (net (code "36") (name "Net-(IC11A--IN)") (class "Default")
      (node (ref "IC11") (pin "8") (pinfunction "-IN_8") (pintype "input"))
      (node (ref "R56") (pin "1") (pinfunction "1_1") (pintype "passive"))
      (node (ref "R58") (pin "2") (pinfunction "2_2") (pintype "passive"))
    )
    (net (code "37") (name "Net-(IC11A-OUT)") (class "Default")
      (node (ref "IC11") (pin "7") (pinfunction "OUT_7") (pintype "output"))
      (node (ref "R58") (pin "1") (pinfunction "1_1") (pintype "passive"))
      (node (ref "R64") (pin "2") (pinfunction "2_2") (pintype "passive"))
      (node (ref "TP5") (pin "TP") (pinfunction "TP_TP") (pintype "input"))
    )
    (net (code "38") (name "Net-(IC11B-+IN)") (class "Default")
      (node (ref "IC11") (pin "3") (pinfunction "+IN_3") (pintype "input"))
      (node (ref "R60") (pin "1") (pinfunction "1_1") (pintype "passive"))
      (node (ref "R61") (pin "2") (pinfunction "2_2") (pintype "passive"))
    )
    (net (code "39") (name "Net-(IC11B--IN)") (class "Default")
      (node (ref "IC11") (pin "4") (pinfunction "-IN_4") (pintype "input"))
      (node (ref "R62") (pin "2") (pinfunction "2_2") (pintype "passive"))
      (node (ref "R63") (pin "1") (pinfunction "1_1") (pintype "passive"))
    )
    (net (code "40") (name "Net-(IC11B-OUT)") (class "Default")
      (node (ref "IC11") (pin "5") (pinfunction "OUT_5") (pintype "output"))
      (node (ref "R63") (pin "2") (pinfunction "2_2") (pintype "passive"))
      (node (ref "R65") (pin "2") (pinfunction "2_2") (pintype "passive"))
      (node (ref "TP6") (pin "TP") (pinfunction "TP_TP") (pintype "input"))
    )
    (net (code "41") (name "Net-(JP2-Pad3)") (class "Default")
      (node (ref "JP2") (pin "3") (pinfunction "3_3") (pintype "passive"))
      (node (ref "R16") (pin "1") (pinfunction "1_1") (pintype "passive"))
    )
    (net (code "42") (name "Net-(JP2-Pad4)") (class "Default")
      (node (ref "JP2") (pin "4") (pinfunction "4_4") (pintype "passive"))
      (node (ref "R15") (pin "1") (pinfunction "1_1") (pintype "passive"))
    )
    (net (code "43") (name "Net-(JP2-Pad5)") (class "Default")
      (node (ref "JP2") (pin "5") (pinfunction "5_5") (pintype "passive"))
      (node (ref "R17") (pin "1") (pinfunction "1_1") (pintype "passive"))
    )
    (net (code "44") (name "Net-(JP2-Pad6)") (class "Default")
      (node (ref "JP2") (pin "6") (pinfunction "6_6") (pintype "passive"))
      (node (ref "R68") (pin "2") (pinfunction "2_2") (pintype "passive"))
    )
    (net (code "45") (name "Net-(JP2-Pad7)") (class "Default")
      (node (ref "JP2") (pin "7") (pinfunction "7_7") (pintype "passive"))
      (node (ref "R66") (pin "2") (pinfunction "2_2") (pintype "passive"))
    )
    (net (code "46") (name "Net-(JP2-Pad8)") (class "Default")
      (node (ref "JP2") (pin "8") (pinfunction "8_8") (pintype "passive"))
      (node (ref "R67") (pin "2") (pinfunction "2_2") (pintype "passive"))
    )
    (net (code "47") (name "Net-(Q1-PadG)") (class "Default")
      (node (ref "Q1") (pin "G") (pinfunction "G_G") (pintype "passive"))
      (node (ref "R1") (pin "2") (pinfunction "2_2") (pintype "passive"))
    )
    (net (code "48") (name "Net-(Q1-PadS)") (class "Default")
      (node (ref "Q1") (pin "S") (pinfunction "S_S") (pintype "passive"))
      (node (ref "R2") (pin "2") (pinfunction "2_2") (pintype "passive"))
      (node (ref "R3") (pin "2") (pinfunction "2_2") (pintype "passive"))
    )
    (net (code "49") (name "Net-(Q2-PadG)") (class "Default")
      (node (ref "Q2") (pin "G") (pinfunction "G_G") (pintype "passive"))
      (node (ref "R5") (pin "2") (pinfunction "2_2") (pintype "passive"))
    )
    (net (code "50") (name "Net-(Q2-PadS)") (class "Default")
      (node (ref "Q2") (pin "S") (pinfunction "S_S") (pintype "passive"))
      (node (ref "R14") (pin "2") (pinfunction "2_2") (pintype "passive"))
      (node (ref "R6") (pin "2") (pinfunction "2_2") (pintype "passive"))
    )
    (net (code "51") (name "Net-(Q3-PadG)") (class "Default")
      (node (ref "Q3") (pin "G") (pinfunction "G_G") (pintype "passive"))
      (node (ref "R19") (pin "2") (pinfunction "2_2") (pintype "passive"))
    )
    (net (code "52") (name "Net-(Q3-PadS)") (class "Default")
      (node (ref "Q3") (pin "S") (pinfunction "S_S") (pintype "passive"))
      (node (ref "R20") (pin "2") (pinfunction "2_2") (pintype "passive"))
      (node (ref "R30") (pin "2") (pinfunction "2_2") (pintype "passive"))
    )
    (net (code "53") (name "Net-(Q4-PadG)") (class "Default")
      (node (ref "Q4") (pin "G") (pinfunction "G_G") (pintype "passive"))
      (node (ref "R22") (pin "2") (pinfunction "2_2") (pintype "passive"))
    )
    (net (code "54") (name "Net-(Q4-PadS)") (class "Default")
      (node (ref "Q4") (pin "S") (pinfunction "S_S") (pintype "passive"))
      (node (ref "R23") (pin "2") (pinfunction "2_2") (pintype "passive"))
      (node (ref "R40") (pin "2") (pinfunction "2_2") (pintype "passive"))
    )
    (net (code "55") (name "Net-(R18-Pad2)") (class "Default")
      (node (ref "R18") (pin "2") (pinfunction "2_2") (pintype "passive"))
      (node (ref "R2") (pin "1") (pinfunction "1_1") (pintype "passive"))
      (node (ref "R20") (pin "1") (pinfunction "1_1") (pintype "passive"))
      (node (ref "R23") (pin "1") (pinfunction "1_1") (pintype "passive"))
      (node (ref "R31") (pin "2") (pinfunction "2_2") (pintype "passive"))
      (node (ref "R37") (pin "P$2") (pinfunction "P$2_P$2") (pintype "bidirectional"))
      (node (ref "R4") (pin "2") (pinfunction "2_2") (pintype "passive"))
      (node (ref "R41") (pin "2") (pinfunction "2_2") (pintype "passive"))
      (node (ref "R57") (pin "2") (pinfunction "2_2") (pintype "passive"))
      (node (ref "R6") (pin "1") (pinfunction "1_1") (pintype "passive"))
    )
    (net (code "56") (name "Net-(R60-Pad2)") (class "Default")
      (node (ref "R60") (pin "2") (pinfunction "2_2") (pintype "passive"))
      (node (ref "U_SENSE") (pin "2") (pinfunction "2_2") (pintype "passive"))
    )
    (net (code "57") (name "Net-(R62-Pad1)") (class "Default")
      (node (ref "R62") (pin "1") (pinfunction "1_1") (pintype "passive"))
      (node (ref "U_SENSE") (pin "1") (pinfunction "1_1") (pintype "passive"))
    )
    (net (code "58") (name "Net-(U1-DIN)") (class "Default")
      (node (ref "R15") (pin "2") (pinfunction "2_2") (pintype "passive"))
      (node (ref "U1") (pin "4") (pinfunction "DIN_4") (pintype "bidirectional"))
    )
    (net (code "59") (name "Net-(U1-OUT)") (class "Default")
      (node (ref "R51") (pin "2") (pinfunction "2_2") (pintype "passive"))
      (node (ref "U1") (pin "6") (pinfunction "OUT_6") (pintype "bidirectional"))
    )
    (net (code "60") (name "Net-(U1-REF)") (class "Default")
      (node (ref "C5") (pin "1") (pinfunction "1_1") (pintype "passive"))
      (node (ref "R49") (pin "2") (pinfunction "2_2") (pintype "passive"))
      (node (ref "TP8") (pin "TP") (pinfunction "TP_TP") (pintype "input"))
      (node (ref "U1") (pin "1") (pinfunction "REF_1") (pintype "bidirectional"))
      (node (ref "U2") (pin "5") (pinfunction "OUTS_5") (pintype "bidirectional"))
      (node (ref "U2") (pin "6") (pinfunction "OUTF_6") (pintype "bidirectional"))
      (node (ref "U3") (pin "6") (pinfunction "REF_6") (pintype "bidirectional"))
    )
    (net (code "61") (name "Net-(U1-SCLK)") (class "Default")
      (node (ref "R16") (pin "2") (pinfunction "2_2") (pintype "passive"))
      (node (ref "U1") (pin "3") (pinfunction "SCLK_3") (pintype "bidirectional"))
      (node (ref "U3") (pin "10") (pinfunction "SCLK_10") (pintype "bidirectional"))
    )
    (net (code "62") (name "Net-(U1-{slash}CS)") (class "Default")
      (node (ref "R17") (pin "2") (pinfunction "2_2") (pintype "passive"))
      (node (ref "U1") (pin "2") (pinfunction "/CS_2") (pintype "bidirectional"))
    )
    (net (code "63") (name "Net-(U2-FILTER)") (class "Default")
      (node (ref "C7") (pin "1") (pinfunction "1_1") (pintype "passive"))
      (node (ref "U2") (pin "1") (pinfunction "FILTER_1") (pintype "bidirectional"))
    )
    (net (code "64") (name "Net-(U3-DOUT)") (class "Default")
      (node (ref "R67") (pin "1") (pinfunction "1_1") (pintype "passive"))
      (node (ref "U3") (pin "1") (pinfunction "DOUT_1") (pintype "bidirectional"))
    )
    (net (code "65") (name "Net-(U3-{slash}CS)") (class "Default")
      (node (ref "R66") (pin "1") (pinfunction "1_1") (pintype "passive"))
      (node (ref "U3") (pin "9") (pinfunction "/CS_9") (pintype "bidirectional"))
    )
    (net (code "66") (name "Net-(U4-+IN)") (class "Default")
      (node (ref "R3") (pin "1") (pinfunction "1_1") (pintype "passive"))
      (node (ref "R8") (pin "2") (pinfunction "2_2") (pintype "passive"))
      (node (ref "U4") (pin "3") (pinfunction "+IN_3") (pintype "input"))
    )
    (net (code "67") (name "Net-(U4--IN)") (class "Default")
      (node (ref "R4") (pin "1") (pinfunction "1_1") (pintype "passive"))
      (node (ref "R7") (pin "2") (pinfunction "2_2") (pintype "passive"))
      (node (ref "U4") (pin "2") (pinfunction "-IN_2") (pintype "input"))
    )
    (net (code "68") (name "Net-(U4-OUT)") (class "Default")
      (node (ref "R10") (pin "1") (pinfunction "1_1") (pintype "passive"))
      (node (ref "R7") (pin "1") (pinfunction "1_1") (pintype "passive"))
      (node (ref "TP1") (pin "TP") (pinfunction "TP_TP") (pintype "input"))
      (node (ref "U4") (pin "6") (pinfunction "OUT_6") (pintype "bidirectional"))
    )
    (net (code "69") (name "Net-(U5-+IN)") (class "Default")
      (node (ref "R14") (pin "1") (pinfunction "1_1") (pintype "passive"))
      (node (ref "R24") (pin "2") (pinfunction "2_2") (pintype "passive"))
      (node (ref "U5") (pin "3") (pinfunction "+IN_3") (pintype "input"))
    )
    (net (code "70") (name "Net-(U5--IN)") (class "Default")
      (node (ref "R18") (pin "1") (pinfunction "1_1") (pintype "passive"))
      (node (ref "R21") (pin "2") (pinfunction "2_2") (pintype "passive"))
      (node (ref "U5") (pin "2") (pinfunction "-IN_2") (pintype "input"))
    )
    (net (code "71") (name "Net-(U5-OUT)") (class "Default")
      (node (ref "R21") (pin "1") (pinfunction "1_1") (pintype "passive"))
      (node (ref "R26") (pin "1") (pinfunction "1_1") (pintype "passive"))
      (node (ref "TP2") (pin "TP") (pinfunction "TP_TP") (pintype "input"))
      (node (ref "U5") (pin "6") (pinfunction "OUT_6") (pintype "bidirectional"))
    )
    (net (code "72") (name "Net-(U6-+IN)") (class "Default")
      (node (ref "R30") (pin "1") (pinfunction "1_1") (pintype "passive"))
      (node (ref "R33") (pin "2") (pinfunction "2_2") (pintype "passive"))
      (node (ref "U6") (pin "3") (pinfunction "+IN_3") (pintype "input"))
    )
    (net (code "73") (name "Net-(U6--IN)") (class "Default")
      (node (ref "R31") (pin "1") (pinfunction "1_1") (pintype "passive"))
      (node (ref "R32") (pin "2") (pinfunction "2_2") (pintype "passive"))
      (node (ref "U6") (pin "2") (pinfunction "-IN_2") (pintype "input"))
    )
    (net (code "74") (name "Net-(U6-OUT)") (class "Default")
      (node (ref "R32") (pin "1") (pinfunction "1_1") (pintype "passive"))
      (node (ref "R35") (pin "1") (pinfunction "1_1") (pintype "passive"))
      (node (ref "TP3") (pin "TP") (pinfunction "TP_TP") (pintype "input"))
      (node (ref "U6") (pin "6") (pinfunction "OUT_6") (pintype "bidirectional"))
    )
    (net (code "75") (name "Net-(U7-+IN)") (class "Default")
      (node (ref "R40") (pin "1") (pinfunction "1_1") (pintype "passive"))
      (node (ref "R43") (pin "2") (pinfunction "2_2") (pintype "passive"))
      (node (ref "U7") (pin "3") (pinfunction "+IN_3") (pintype "input"))
    )
    (net (code "76") (name "Net-(U7--IN)") (class "Default")
      (node (ref "R41") (pin "1") (pinfunction "1_1") (pintype "passive"))
      (node (ref "R42") (pin "2") (pinfunction "2_2") (pintype "passive"))
      (node (ref "U7") (pin "2") (pinfunction "-IN_2") (pintype "input"))
    )
    (net (code "77") (name "Net-(U7-OUT)") (class "Default")
      (node (ref "R42") (pin "1") (pinfunction "1_1") (pintype "passive"))
      (node (ref "R45") (pin "1") (pinfunction "1_1") (pintype "passive"))
      (node (ref "TP4") (pin "TP") (pinfunction "TP_TP") (pintype "input"))
      (node (ref "U7") (pin "6") (pinfunction "OUT_6") (pintype "bidirectional"))
    )
    (net (code "78") (name "unconnected-(U4-REFCLK-Pad5)") (class "Default")
      (node (ref "U4") (pin "5") (pinfunction "REFCLK_5") (pintype "bidirectional"))
    )
    (net (code "79") (name "unconnected-(U5-REFCLK-Pad5)") (class "Default")
      (node (ref "U5") (pin "5") (pinfunction "REFCLK_5") (pintype "bidirectional"))
    )
    (net (code "80") (name "unconnected-(U6-REFCLK-Pad5)") (class "Default")
      (node (ref "U6") (pin "5") (pinfunction "REFCLK_5") (pintype "bidirectional"))
    )
    (net (code "81") (name "unconnected-(U7-REFCLK-Pad5)") (class "Default")
      (node (ref "U7") (pin "5") (pinfunction "REFCLK_5") (pintype "bidirectional"))
    )
  )
)
